# Sheet1.net
KiCad netlist of a schematic drawn in Altium Designer
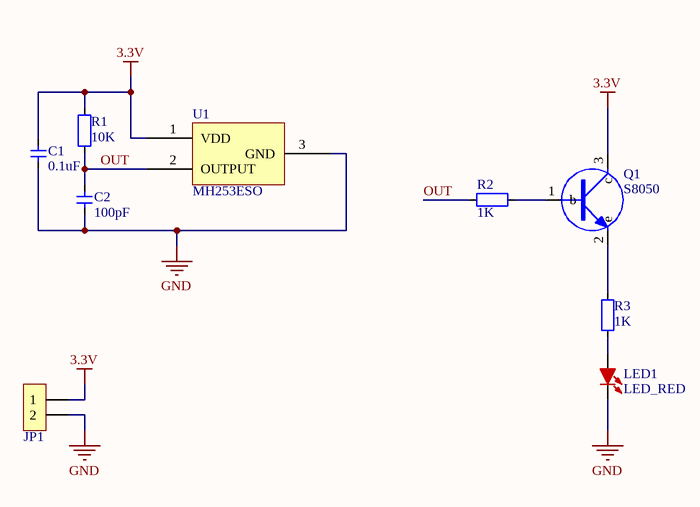
[diagram p0: Sheet1.SchDoc]

(export (version "E")
  (design (tool "Eeschema 10.0.6"))
  (components
    (comp (ref "C1")
      (value "0.1uF")
      (footprint "C 0603")
      (description "无极性贴片电容")
      (fields (field (name "版权归属") "源创客"))
      (libsource (lib "电容") (part "C"))
    )
    (comp (ref "C2")
      (value "100pF")
      (footprint "C 0603")
      (description "无极性贴片电容")
      (fields (field (name "版权归属") "源创客"))
      (libsource (lib "电容") (part "C"))
    )
    (comp (ref "JP1")
      (value "HDR-1X2")
      (footprint "HDR-1X2")
      (description "2P接插件")
      (fields (field (name "版权归属") "源创客"))
      (libsource (lib "排针-排母") (part "Header 2"))
    )
    (comp (ref "LED1") (value "LED_RED") (footprint "LED 0603B") (libsource (lib "LED") (part "LED_RED")))
    (comp (ref "Q1") (value "S8050") (footprint "SOT23-3L") (libsource (lib "三极管") (part "NPN")))
    (comp (ref "R1")
      (value "10K")
      (footprint "R 0603")
      (description "贴片电阻")
      (fields (field (name "版权归属") "源创客"))
      (libsource (lib "电阻") (part "R"))
    )
    (comp (ref "R2")
      (value "1K")
      (footprint "R 0603")
      (description "贴片电阻")
      (fields (field (name "版权归属") "源创客"))
      (libsource (lib "") (part "R_1"))
    )
    (comp (ref "R3")
      (value "1K")
      (footprint "R 0603")
      (description "贴片电阻")
      (fields (field (name "版权归属") "源创客"))
      (libsource (lib "电阻") (part "R"))
    )
    (comp (ref "U1")
      (value "MH253ESO")
      (footprint "MH253ESO")
      (description "全极霍尔效应开关")
      (libsource (lib "传感器") (part "MH253ESO"))
    )
  )
  (nets
    (net (code "1") (name "/OUT") (class "Default")
      (node (ref "C2") (pin "2") (pinfunction "2_2") (pintype "passive"))
      (node (ref "R1") (pin "1") (pinfunction "1_1") (pintype "passive"))
      (node (ref "R2") (pin "1") (pinfunction "1_1") (pintype "passive"))
      (node (ref "U1") (pin "2") (pinfunction "OUTPUT_2") (pintype "passive"))
    )
    (net (code "2") (name "3.3V") (class "Default")
      (node (ref "C1") (pin "2") (pinfunction "2_2") (pintype "passive"))
      (node (ref "JP1") (pin "1") (pinfunction "1_1") (pintype "passive"))
      (node (ref "Q1") (pin "3") (pinfunction "c_3") (pintype "passive"))
      (node (ref "R1") (pin "2") (pinfunction "2_2") (pintype "passive"))
      (node (ref "U1") (pin "1") (pinfunction "VDD_1") (pintype "passive"))
    )
    (net (code "3") (name "GND") (class "Default")
      (node (ref "C1") (pin "1") (pinfunction "1_1") (pintype "passive"))
      (node (ref "C2") (pin "1") (pinfunction "1_1") (pintype "passive"))
      (node (ref "JP1") (pin "2") (pinfunction "2_2") (pintype "passive"))
      (node (ref "LED1") (pin "2") (pinfunction "K_2") (pintype "passive"))
      (node (ref "U1") (pin "3") (pinfunction "GND_3") (pintype "passive"))
    )
    (net (code "4") (name "Net-(LED1-A)") (class "Default")
      (node (ref "LED1") (pin "1") (pinfunction "A_1") (pintype "passive"))
      (node (ref "R3") (pin "1") (pinfunction "1_1") (pintype "passive"))
    )
    (net (code "5") (name "Net-(Q1-b)") (class "Default")
      (node (ref "Q1") (pin "1") (pinfunction "b_1") (pintype "passive"))
      (node (ref "R2") (pin "2") (pinfunction "2_2") (pintype "passive"))
    )
    (net (code "6") (name "Net-(Q1-e)") (class "Default")
      (node (ref "Q1") (pin "2") (pinfunction "e_2") (pintype "passive"))
      (node (ref "R3") (pin "2") (pinfunction "2_2") (pintype "passive"))
    )
  )
)
